# sch_main.net
KiCad netlist of a schematic drawn in Altium Designer
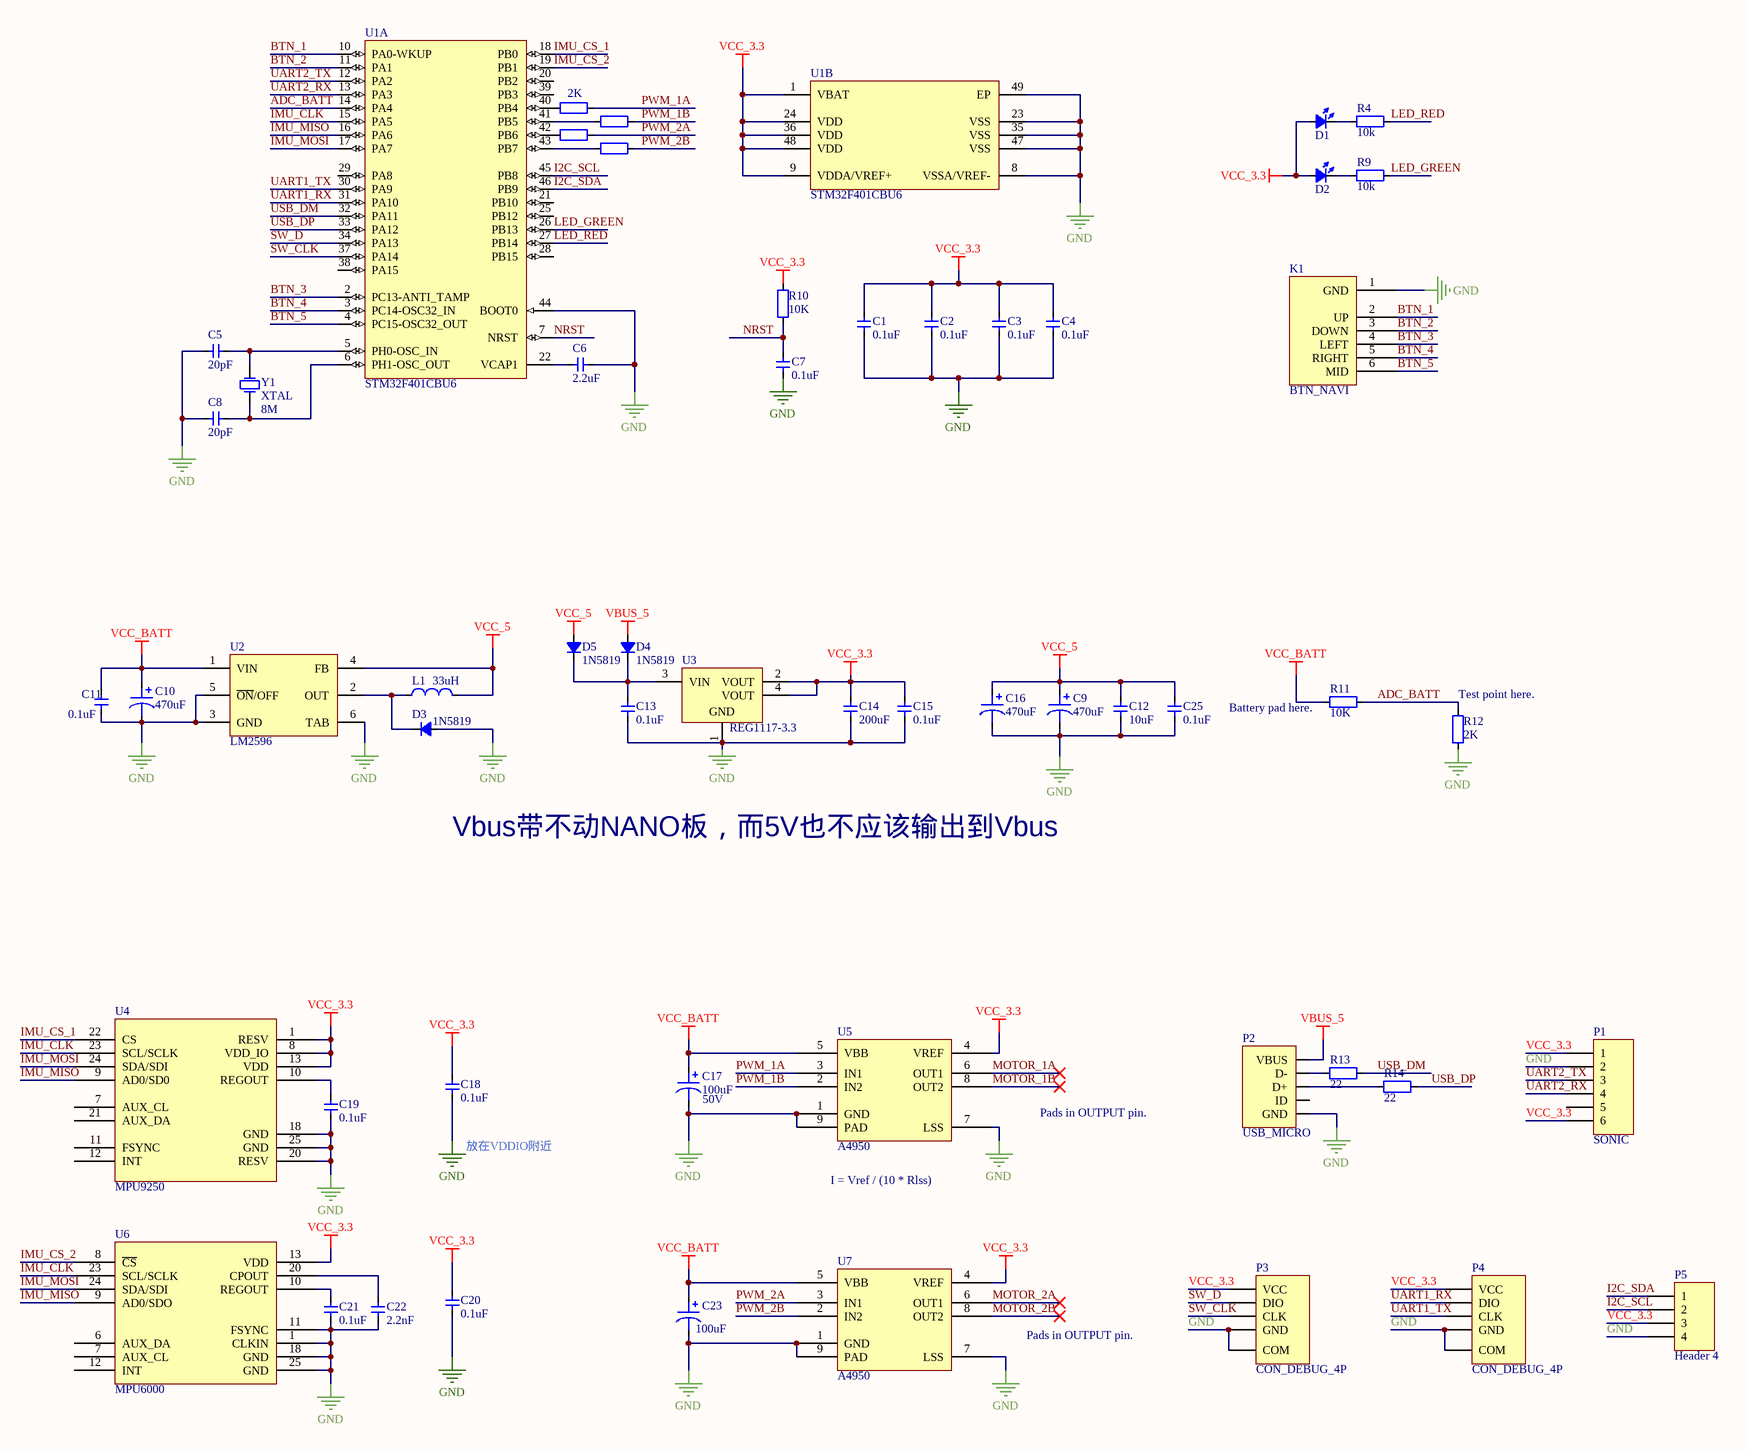
[diagram p0: sch_main.SchDoc]

(export (version "E")
  (design (tool "Eeschema 10.0.6"))
  (components
    (comp (ref "C1")
      (value "0.1uF")
      (footprint "CAP_0603")
      (description "Capacity")
      (fields (field (name "Comment") "CAP"))
      (libsource (lib "Charles") (part "CAP"))
    )
    (comp (ref "C2")
      (value "0.1uF")
      (footprint "CAP_0603")
      (description "Capacity")
      (fields (field (name "Comment") "CAP"))
      (libsource (lib "Charles") (part "CAP"))
    )
    (comp (ref "C3")
      (value "0.1uF")
      (footprint "CAP_0603")
      (description "Capacity")
      (fields (field (name "Comment") "CAP"))
      (libsource (lib "Charles") (part "CAP"))
    )
    (comp (ref "C4")
      (value "0.1uF")
      (footprint "CAP_0603")
      (description "Capacity")
      (fields (field (name "Comment") "CAP"))
      (libsource (lib "Charles") (part "CAP"))
    )
    (comp (ref "C5")
      (value "20pF")
      (footprint "CAP_0603")
      (description "Capacity")
      (fields (field (name "Comment") "CAP"))
      (libsource (lib "Charles") (part "CAP"))
    )
    (comp (ref "C6")
      (value "2.2uF")
      (footprint "CAP_0603")
      (description "Capacity")
      (fields (field (name "Comment") "CAP"))
      (libsource (lib "Charles") (part "CAP"))
    )
    (comp (ref "C7")
      (value "0.1uF")
      (footprint "CAP_0603")
      (description "Capacity")
      (fields (field (name "Comment") "CAP"))
      (libsource (lib "Charles") (part "CAP"))
    )
    (comp (ref "C8")
      (value "20pF")
      (footprint "CAP_0603")
      (description "Capacity")
      (fields (field (name "Comment") "CAP"))
      (libsource (lib "Charles") (part "CAP"))
    )
    (comp (ref "C9")
      (value "470uF")
      (footprint "CAP ALUM 6.6MM")
      (description "SMT Polarised Capacitor")
      (libsource (lib "Charles") (part "CAP_POL"))
    )
    (comp (ref "C10")
      (value "470uF")
      (footprint "CAP ALUM 6.6MM")
      (description "SMT Polarised Capacitor")
      (libsource (lib "Charles") (part "CAP_POL"))
    )
    (comp (ref "C11")
      (value "0.1uF")
      (footprint "CAP_0805")
      (description "Capacity")
      (fields (field (name "Comment") "CAP"))
      (libsource (lib "Charles") (part "CAP"))
    )
    (comp (ref "C12")
      (value "10uF")
      (footprint "CAP_TAN_B1210")
      (description "Capacity")
      (fields (field (name "Comment") "CAP"))
      (libsource (lib "Charles") (part "CAP"))
    )
    (comp (ref "C13")
      (value "0.1uF")
      (footprint "CAP_0805")
      (description "Capacity")
      (fields (field (name "Comment") "CAP"))
      (libsource (lib "Charles") (part "CAP"))
    )
    (comp (ref "C14")
      (value "200uF")
      (footprint "CAP_0805")
      (description "Capacity")
      (fields (field (name "Comment") "CAP"))
      (libsource (lib "Charles") (part "CAP"))
    )
    (comp (ref "C15")
      (value "0.1uF")
      (footprint "CAP_0603")
      (description "Capacity")
      (fields (field (name "Comment") "CAP"))
      (libsource (lib "Charles") (part "CAP"))
    )
    (comp (ref "C16")
      (value "470uF")
      (footprint "CAP ALUM 6.6MM")
      (description "SMT Polarised Capacitor")
      (libsource (lib "Charles") (part "CAP_POL"))
    )
    (comp (ref "C17")
      (value "100uF")
      (footprint "CAP ALUM 6.6MM")
      (description "SMT Polarised Capacitor")
      (fields (field (name "VOLTAGE") "50V"))
      (libsource (lib "Charles") (part "CAP_POL"))
    )
    (comp (ref "C18")
      (value "0.1uF")
      (footprint "CAP_0603")
      (description "Capacity")
      (fields (field (name "Comment") "CAP"))
      (libsource (lib "Charles") (part "CAP"))
    )
    (comp (ref "C19")
      (value "0.1uF")
      (footprint "CAP_0603")
      (description "Capacity")
      (fields (field (name "Comment") "CAP"))
      (libsource (lib "Charles") (part "CAP"))
    )
    (comp (ref "C20")
      (value "0.1uF")
      (footprint "CAP_0603")
      (description "Capacity")
      (fields (field (name "Comment") "CAP"))
      (libsource (lib "Charles") (part "CAP"))
    )
    (comp (ref "C21")
      (value "0.1uF")
      (footprint "CAP_0603")
      (description "Capacity")
      (fields (field (name "Comment") "CAP"))
      (libsource (lib "Charles") (part "CAP"))
    )
    (comp (ref "C22")
      (value "2.2nF")
      (footprint "CAP_0603")
      (description "Capacity")
      (fields (field (name "Comment") "CAP"))
      (libsource (lib "Charles") (part "CAP"))
    )
    (comp (ref "C23")
      (value "100uF")
      (footprint "CAP ALUM 6.6MM")
      (description "SMT Polarised Capacitor")
      (fields (field (name "VOLTAGE") "50V"))
      (libsource (lib "Charles") (part "CAP_POL"))
    )
    (comp (ref "C25")
      (value "0.1uF")
      (footprint "CAP_0603")
      (description "Capacity")
      (fields (field (name "Comment") "CAP"))
      (libsource (lib "Charles") (part "CAP"))
    )
    (comp (ref "D1") (value "LED") (footprint "LED_0603_GREEN") (libsource (lib "Charles") (part "LED")))
    (comp (ref "D2") (value "LED") (footprint "LED_0603_GREEN") (libsource (lib "Charles") (part "LED")))
    (comp (ref "D3")
      (value "1N5819")
      (footprint "DIO_SOD-123")
      (description "Diode")
      (libsource (lib "Charles") (part "Diode"))
    )
    (comp (ref "D4")
      (value "1N5819")
      (footprint "DIO_SOD-123")
      (description "Diode")
      (libsource (lib "Charles") (part "Diode"))
    )
    (comp (ref "D5")
      (value "1N5819")
      (footprint "DIO_SOD-123")
      (description "Diode")
      (libsource (lib "Charles") (part "Diode"))
    )
    (comp (ref "K1")
      (value "BTN_NAVI")
      (footprint "BTN_NAVI_10x10")
      (libsource (lib "Charles") (part "BTN_NAVI"))
    )
    (comp (ref "L1")
      (value "33uH")
      (footprint "IND_CDRH74")
      (description "Inductor")
      (fields (field (name "Comment") "IND"))
      (libsource (lib "Charles") (part "IND"))
    )
    (comp (ref "P1")
      (value "SONIC")
      (footprint "HDR1X6")
      (description "Header, 6-Pin")
      (fields (field (name "PUBLISHER") "Altium Limited"))
      (libsource (lib "Miscellaneous Connectors") (part "Header 6"))
    )
    (comp (ref "P2")
      (value "USB_MICRO")
      (footprint "USB_MICRO")
      (libsource (lib "Charles") (part "USB_MICRO"))
    )
    (comp (ref "P3")
      (value "CON_DEBUG_4P")
      (footprint "CON_DEBUG_4P_STD")
      (libsource (lib "Charles") (part "CON_DEBUG_4P"))
    )
    (comp (ref "P4")
      (value "CON_DEBUG_4P")
      (footprint "CON_DEBUG_4P_STD")
      (libsource (lib "Charles") (part "CON_DEBUG_4P"))
    )
    (comp (ref "P5")
      (value "Header 4")
      (footprint "HDR1X4")
      (description "Header, 4-Pin")
      (fields (field (name "PUBLISHER") "Altium Limited"))
      (libsource (lib "Miscellaneous Connectors") (part "Header 4"))
    )
    (comp (ref "R1")
      (value "2K")
      (footprint "RES_0603")
      (description "Resister")
      (fields (field (name "Comment") "RES"))
      (libsource (lib "Charles") (part "RES"))
    )
    (comp (ref "R3")
      (value "RES")
      (footprint "RES_0603")
      (description "Resister")
      (libsource (lib "Charles") (part "RES"))
    )
    (comp (ref "R4")
      (value "10k")
      (footprint "RES_0603")
      (description "Resister")
      (fields (field (name "Comment") "RES"))
      (libsource (lib "") (part "RES_2"))
    )
    (comp (ref "R6")
      (value "RES")
      (footprint "RES_0603")
      (description "Resister")
      (libsource (lib "Charles") (part "RES"))
    )
    (comp (ref "R8")
      (value "RES")
      (footprint "RES_0603")
      (description "Resister")
      (libsource (lib "Charles") (part "RES"))
    )
    (comp (ref "R9")
      (value "10k")
      (footprint "RES_0603")
      (description "Resister")
      (fields (field (name "Comment") "RES"))
      (libsource (lib "") (part "RES_2"))
    )
    (comp (ref "R10")
      (value "10K")
      (footprint "RES_0603")
      (description "Resister")
      (fields (field (name "Comment") "RES"))
      (libsource (lib "") (part "RES_1"))
    )
    (comp (ref "R11")
      (value "10K")
      (footprint "RES_0603")
      (description "Resister")
      (fields (field (name "Comment") "RES"))
      (libsource (lib "Charles") (part "RES"))
    )
    (comp (ref "R12")
      (value "2K")
      (footprint "RES_0603")
      (description "Resister")
      (fields (field (name "Comment") "RES"))
      (libsource (lib "") (part "RES_3"))
    )
    (comp (ref "R13")
      (value "22")
      (footprint "RES_0603")
      (description "Resister")
      (fields (field (name "Comment") "RES"))
      (libsource (lib "Charles") (part "RES"))
    )
    (comp (ref "R14")
      (value "22")
      (footprint "RES_0603")
      (description "Resister")
      (fields (field (name "Comment") "RES"))
      (libsource (lib "Charles") (part "RES"))
    )
    (comp (ref "U1")
      (value "STM32F401CBU6")
      (footprint "STM-UFQFPN48_N")
      (fields (field (name "MANUFACTURER") "STMicroelectronics"))
      (libsource (lib "STMicroelectronics STM32 F4") (part "STM32F401CBU6"))
    )
    (comp (ref "U2")
      (value "LM2596")
      (footprint "LM2596")
      (description "Power")
      (libsource (lib "Charles") (part "LM2596"))
    )
    (comp (ref "U3")
      (value "REG1117-3.3")
      (footprint "TI-DCY4_N")
      (fields (field (name "MANUFACTURER") "Texas Instruments"))
      (libsource (lib "TI Power Management Linear Regulator Single Channel LDO (400-7500mA)") (part "REG1117-3.3"))
    )
    (comp (ref "U4")
      (value "MPU9250")
      (footprint "MPU9250")
      (description "Sensor")
      (libsource (lib "Charles") (part "MPU9250"))
    )
    (comp (ref "U5")
      (value "A4950")
      (footprint "A4950")
      (description "Dual N-MOS, 40V, 3.5A.")
      (libsource (lib "Charles") (part "A4950"))
    )
    (comp (ref "U6")
      (value "MPU6000")
      (footprint "MPU6000")
      (description "IMU 6axis, (左下方引脚全部悬空)")
      (libsource (lib "Charles") (part "MPU6000"))
    )
    (comp (ref "U7")
      (value "A4950")
      (footprint "A4950")
      (description "Dual N-MOS, 40V, 3.5A.")
      (libsource (lib "Charles") (part "A4950"))
    )
    (comp (ref "Y1")
      (value "XTAL")
      (footprint "XTAL_8M")
      (fields (field (name "FREQUENCY") "8M"))
      (libsource (lib "Charles") (part "XTAL"))
    )
  )
  (nets
    (net (code "1") (name "/ADC_BATT") (class "Default")
      (node (ref "R11") (pin "2") (pinfunction "2_2") (pintype "passive"))
      (node (ref "R12") (pin "1") (pinfunction "1_1") (pintype "passive"))
      (node (ref "U1") (pin "14") (pinfunction "PA4_14") (pintype "bidirectional"))
    )
    (net (code "2") (name "/BTN_1") (class "Default")
      (node (ref "K1") (pin "2") (pinfunction "UP_2") (pintype "passive"))
      (node (ref "U1") (pin "10") (pinfunction "PA0-WKUP_10") (pintype "bidirectional"))
    )
    (net (code "3") (name "/BTN_2") (class "Default")
      (node (ref "K1") (pin "3") (pinfunction "DOWN_3") (pintype "passive"))
      (node (ref "U1") (pin "11") (pinfunction "PA1_11") (pintype "bidirectional"))
    )
    (net (code "4") (name "/BTN_3") (class "Default")
      (node (ref "K1") (pin "4") (pinfunction "LEFT_4") (pintype "passive"))
      (node (ref "U1") (pin "2") (pinfunction "PC13-ANTI_TAMP_2") (pintype "bidirectional"))
    )
    (net (code "5") (name "/BTN_4") (class "Default")
      (node (ref "K1") (pin "5") (pinfunction "RIGHT_5") (pintype "passive"))
      (node (ref "U1") (pin "3") (pinfunction "PC14-OSC32_IN_3") (pintype "bidirectional"))
    )
    (net (code "6") (name "/BTN_5") (class "Default")
      (node (ref "K1") (pin "6") (pinfunction "MID_6") (pintype "passive"))
      (node (ref "U1") (pin "4") (pinfunction "PC15-OSC32_OUT_4") (pintype "bidirectional"))
    )
    (net (code "7") (name "/I2C_SCL") (class "Default")
      (node (ref "P5") (pin "2") (pinfunction "2_2") (pintype "passive"))
      (node (ref "U1") (pin "45") (pinfunction "PB8_45") (pintype "bidirectional"))
    )
    (net (code "8") (name "/I2C_SDA") (class "Default")
      (node (ref "P5") (pin "1") (pinfunction "1_1") (pintype "passive"))
      (node (ref "U1") (pin "46") (pinfunction "PB9_46") (pintype "bidirectional"))
    )
    (net (code "9") (name "/IMU_CLK") (class "Default")
      (node (ref "U1") (pin "15") (pinfunction "PA5_15") (pintype "bidirectional"))
      (node (ref "U4") (pin "23") (pinfunction "SCL/SCLK_23") (pintype "passive"))
      (node (ref "U6") (pin "23") (pinfunction "SCL/SCLK_23") (pintype "passive"))
    )
    (net (code "10") (name "/IMU_CS_1") (class "Default")
      (node (ref "U1") (pin "18") (pinfunction "PB0_18") (pintype "bidirectional"))
      (node (ref "U4") (pin "22") (pinfunction "CS_22") (pintype "passive"))
    )
    (net (code "11") (name "/IMU_CS_2") (class "Default")
      (node (ref "U1") (pin "19") (pinfunction "PB1_19") (pintype "bidirectional"))
      (node (ref "U6") (pin "8") (pinfunction "~{CS}_8") (pintype "passive"))
    )
    (net (code "12") (name "/IMU_MISO") (class "Default")
      (node (ref "U1") (pin "16") (pinfunction "PA6_16") (pintype "bidirectional"))
      (node (ref "U4") (pin "9") (pinfunction "AD0/SD0_9") (pintype "passive"))
      (node (ref "U6") (pin "9") (pinfunction "AD0/SDO_9") (pintype "passive"))
    )
    (net (code "13") (name "/IMU_MOSI") (class "Default")
      (node (ref "U1") (pin "17") (pinfunction "PA7_17") (pintype "bidirectional"))
      (node (ref "U4") (pin "24") (pinfunction "SDA/SDI_24") (pintype "passive"))
      (node (ref "U6") (pin "24") (pinfunction "SDA/SDI_24") (pintype "passive"))
    )
    (net (code "14") (name "/LED_GREEN") (class "Default")
      (node (ref "R9") (pin "1") (pinfunction "1_1") (pintype "passive"))
      (node (ref "U1") (pin "26") (pinfunction "PB13_26") (pintype "bidirectional"))
    )
    (net (code "15") (name "/LED_RED") (class "Default")
      (node (ref "R4") (pin "1") (pinfunction "1_1") (pintype "passive"))
      (node (ref "U1") (pin "27") (pinfunction "PB14_27") (pintype "bidirectional"))
    )
    (net (code "16") (name "/MOTOR_1A") (class "Default")
      (node (ref "U5") (pin "6") (pinfunction "OUT1_6") (pintype "passive+no_connect"))
    )
    (net (code "17") (name "/MOTOR_1B") (class "Default")
      (node (ref "U5") (pin "8") (pinfunction "OUT2_8") (pintype "passive+no_connect"))
    )
    (net (code "18") (name "/MOTOR_2A") (class "Default")
      (node (ref "U7") (pin "6") (pinfunction "OUT1_6") (pintype "passive+no_connect"))
    )
    (net (code "19") (name "/MOTOR_2B") (class "Default")
      (node (ref "U7") (pin "8") (pinfunction "OUT2_8") (pintype "passive+no_connect"))
    )
    (net (code "20") (name "/NRST") (class "Default")
      (node (ref "C7") (pin "2") (pinfunction "2_2") (pintype "passive"))
      (node (ref "R10") (pin "1") (pinfunction "1_1") (pintype "passive"))
      (node (ref "U1") (pin "7") (pinfunction "NRST_7") (pintype "bidirectional"))
    )
    (net (code "21") (name "/PWM_1A") (class "Default")
      (node (ref "R1") (pin "2") (pinfunction "2_2") (pintype "passive"))
      (node (ref "U5") (pin "3") (pinfunction "IN1_3") (pintype "passive"))
    )
    (net (code "22") (name "/PWM_1B") (class "Default")
      (node (ref "R3") (pin "2") (pinfunction "2_2") (pintype "passive"))
      (node (ref "U5") (pin "2") (pinfunction "IN2_2") (pintype "passive"))
    )
    (net (code "23") (name "/PWM_2A") (class "Default")
      (node (ref "R6") (pin "2") (pinfunction "2_2") (pintype "passive"))
      (node (ref "U7") (pin "3") (pinfunction "IN1_3") (pintype "passive"))
    )
    (net (code "24") (name "/PWM_2B") (class "Default")
      (node (ref "R8") (pin "2") (pinfunction "2_2") (pintype "passive"))
      (node (ref "U7") (pin "2") (pinfunction "IN2_2") (pintype "passive"))
    )
    (net (code "25") (name "/SW_CLK") (class "Default")
      (node (ref "P3") (pin "3") (pinfunction "CLK_3") (pintype "passive"))
      (node (ref "U1") (pin "37") (pinfunction "PA14_37") (pintype "bidirectional"))
    )
    (net (code "26") (name "/SW_D") (class "Default")
      (node (ref "P3") (pin "2") (pinfunction "DIO_2") (pintype "passive"))
      (node (ref "U1") (pin "34") (pinfunction "PA13_34") (pintype "bidirectional"))
    )
    (net (code "27") (name "/UART1_RX") (class "Default")
      (node (ref "P4") (pin "2") (pinfunction "DIO_2") (pintype "passive"))
      (node (ref "U1") (pin "31") (pinfunction "PA10_31") (pintype "bidirectional"))
    )
    (net (code "28") (name "/UART1_TX") (class "Default")
      (node (ref "P4") (pin "3") (pinfunction "CLK_3") (pintype "passive"))
      (node (ref "U1") (pin "30") (pinfunction "PA9_30") (pintype "bidirectional"))
    )
    (net (code "29") (name "/UART2_RX") (class "Default")
      (node (ref "P1") (pin "4") (pinfunction "4_4") (pintype "passive"))
      (node (ref "U1") (pin "13") (pinfunction "PA3_13") (pintype "bidirectional"))
    )
    (net (code "30") (name "/UART2_TX") (class "Default")
      (node (ref "P1") (pin "3") (pinfunction "3_3") (pintype "passive"))
      (node (ref "U1") (pin "12") (pinfunction "PA2_12") (pintype "bidirectional"))
    )
    (net (code "31") (name "/USB_DM") (class "Default")
      (node (ref "R13") (pin "2") (pinfunction "2_2") (pintype "passive"))
      (node (ref "U1") (pin "32") (pinfunction "PA11_32") (pintype "bidirectional"))
    )
    (net (code "32") (name "/USB_DP") (class "Default")
      (node (ref "R14") (pin "2") (pinfunction "2_2") (pintype "passive"))
      (node (ref "U1") (pin "33") (pinfunction "PA12_33") (pintype "bidirectional"))
    )
    (net (code "33") (name "GND") (class "Default")
      (node (ref "C1") (pin "1") (pinfunction "1_1") (pintype "passive"))
      (node (ref "C10") (pin "2") (pinfunction "2_2") (pintype "passive"))
      (node (ref "C11") (pin "1") (pinfunction "1_1") (pintype "passive"))
      (node (ref "C12") (pin "1") (pinfunction "1_1") (pintype "passive"))
      (node (ref "C13") (pin "1") (pinfunction "1_1") (pintype "passive"))
      (node (ref "C14") (pin "1") (pinfunction "1_1") (pintype "passive"))
      (node (ref "C15") (pin "1") (pinfunction "1_1") (pintype "passive"))
      (node (ref "C16") (pin "2") (pinfunction "2_2") (pintype "passive"))
      (node (ref "C17") (pin "2") (pinfunction "2_2") (pintype "passive"))
      (node (ref "C18") (pin "1") (pinfunction "1_1") (pintype "passive"))
      (node (ref "C19") (pin "1") (pinfunction "1_1") (pintype "passive"))
      (node (ref "C2") (pin "1") (pinfunction "1_1") (pintype "passive"))
      (node (ref "C20") (pin "1") (pinfunction "1_1") (pintype "passive"))
      (node (ref "C21") (pin "1") (pinfunction "1_1") (pintype "passive"))
      (node (ref "C22") (pin "1") (pinfunction "1_1") (pintype "passive"))
      (node (ref "C23") (pin "2") (pinfunction "2_2") (pintype "passive"))
      (node (ref "C25") (pin "1") (pinfunction "1_1") (pintype "passive"))
      (node (ref "C3") (pin "1") (pinfunction "1_1") (pintype "passive"))
      (node (ref "C4") (pin "1") (pinfunction "1_1") (pintype "passive"))
      (node (ref "C5") (pin "1") (pinfunction "1_1") (pintype "passive"))
      (node (ref "C6") (pin "2") (pinfunction "2_2") (pintype "passive"))
      (node (ref "C7") (pin "1") (pinfunction "1_1") (pintype "passive"))
      (node (ref "C8") (pin "1") (pinfunction "1_1") (pintype "passive"))
      (node (ref "C9") (pin "2") (pinfunction "2_2") (pintype "passive"))
      (node (ref "D3") (pin "1") (pinfunction "A_1") (pintype "passive"))
      (node (ref "K1") (pin "1") (pinfunction "GND_1") (pintype "passive"))
      (node (ref "P1") (pin "2") (pinfunction "2_2") (pintype "passive"))
      (node (ref "P2") (pin "5") (pinfunction "GND_5") (pintype "passive"))
      (node (ref "P3") (pin "4") (pinfunction "GND_4") (pintype "passive"))
      (node (ref "P3") (pin "5") (pinfunction "COM_5") (pintype "passive"))
      (node (ref "P4") (pin "4") (pinfunction "GND_4") (pintype "passive"))
      (node (ref "P4") (pin "5") (pinfunction "COM_5") (pintype "passive"))
      (node (ref "P5") (pin "4") (pinfunction "4_4") (pintype "passive"))
      (node (ref "R12") (pin "2") (pinfunction "2_2") (pintype "passive"))
      (node (ref "U1") (pin "23") (pinfunction "VSS_23") (pintype "power_in"))
      (node (ref "U1") (pin "35") (pinfunction "VSS_35") (pintype "power_in"))
      (node (ref "U1") (pin "44") (pinfunction "BOOT0_44") (pintype "input"))
      (node (ref "U1") (pin "47") (pinfunction "VSS_47") (pintype "power_in"))
      (node (ref "U1") (pin "49") (pinfunction "EP_49") (pintype "power_in"))
      (node (ref "U1") (pin "8") (pinfunction "VSSA/VREF-_8") (pintype "power_in"))
      (node (ref "U2") (pin "3") (pinfunction "GND_3") (pintype "power_in"))
      (node (ref "U2") (pin "5") (pinfunction "~{ON}/OFF_5") (pintype "passive"))
      (node (ref "U2") (pin "6") (pinfunction "TAB_6") (pintype "power_in"))
      (node (ref "U3") (pin "1") (pinfunction "GND_1") (pintype "power_in"))
      (node (ref "U4") (pin "18") (pinfunction "GND_18") (pintype "passive"))
      (node (ref "U4") (pin "20") (pinfunction "RESV_20") (pintype "passive"))
      (node (ref "U4") (pin "25") (pinfunction "GND_25") (pintype "passive"))
      (node (ref "U5") (pin "1") (pinfunction "GND_1") (pintype "passive"))
      (node (ref "U5") (pin "7") (pinfunction "LSS_7") (pintype "passive"))
      (node (ref "U5") (pin "9") (pinfunction "PAD_9") (pintype "passive"))
      (node (ref "U6") (pin "1") (pinfunction "CLKIN_1") (pintype "passive"))
      (node (ref "U6") (pin "11") (pinfunction "FSYNC_11") (pintype "passive"))
      (node (ref "U6") (pin "18") (pinfunction "GND_18") (pintype "passive"))
      (node (ref "U6") (pin "25") (pinfunction "GND_25") (pintype "passive"))
      (node (ref "U7") (pin "1") (pinfunction "GND_1") (pintype "passive"))
      (node (ref "U7") (pin "7") (pinfunction "LSS_7") (pintype "passive"))
      (node (ref "U7") (pin "9") (pinfunction "PAD_9") (pintype "passive"))
    )
    (net (code "34") (name "Net-(D1-K)") (class "Default")
      (node (ref "D1") (pin "2") (pinfunction "K_2") (pintype "passive"))
      (node (ref "R4") (pin "2") (pinfunction "2_2") (pintype "passive"))
    )
    (net (code "35") (name "Net-(D2-K)") (class "Default")
      (node (ref "D2") (pin "2") (pinfunction "K_2") (pintype "passive"))
      (node (ref "R9") (pin "2") (pinfunction "2_2") (pintype "passive"))
    )
    (net (code "36") (name "Net-(D3-K)") (class "Default")
      (node (ref "D3") (pin "2") (pinfunction "K_2") (pintype "passive"))
      (node (ref "L1") (pin "1") (pinfunction "1_1") (pintype "passive"))
      (node (ref "U2") (pin "2") (pinfunction "OUT_2") (pintype "power_in"))
    )
    (net (code "37") (name "Net-(D4-K)") (class "Default")
      (node (ref "C13") (pin "2") (pinfunction "2_2") (pintype "passive"))
      (node (ref "D4") (pin "2") (pinfunction "K_2") (pintype "passive"))
      (node (ref "D5") (pin "2") (pinfunction "K_2") (pintype "passive"))
      (node (ref "U3") (pin "3") (pinfunction "VIN_3") (pintype "power_in"))
    )
    (net (code "38") (name "Net-(P2-D+)") (class "Default")
      (node (ref "P2") (pin "3") (pinfunction "D+_3") (pintype "passive"))
      (node (ref "R14") (pin "1") (pinfunction "1_1") (pintype "passive"))
    )
    (net (code "39") (name "Net-(P2-D-)") (class "Default")
      (node (ref "P2") (pin "2") (pinfunction "D-_2") (pintype "passive"))
      (node (ref "R13") (pin "1") (pinfunction "1_1") (pintype "passive"))
    )
    (net (code "40") (name "Net-(U1A-PB4)") (class "Default")
      (node (ref "R1") (pin "1") (pinfunction "1_1") (pintype "passive"))
      (node (ref "U1") (pin "40") (pinfunction "PB4_40") (pintype "bidirectional"))
    )
    (net (code "41") (name "Net-(U1A-PB5)") (class "Default")
      (node (ref "R3") (pin "1") (pinfunction "1_1") (pintype "passive"))
      (node (ref "U1") (pin "41") (pinfunction "PB5_41") (pintype "bidirectional"))
    )
    (net (code "42") (name "Net-(U1A-PB6)") (class "Default")
      (node (ref "R6") (pin "1") (pinfunction "1_1") (pintype "passive"))
      (node (ref "U1") (pin "42") (pinfunction "PB6_42") (pintype "bidirectional"))
    )
    (net (code "43") (name "Net-(U1A-PB7)") (class "Default")
      (node (ref "R8") (pin "1") (pinfunction "1_1") (pintype "passive"))
      (node (ref "U1") (pin "43") (pinfunction "PB7_43") (pintype "bidirectional"))
    )
    (net (code "44") (name "Net-(U1A-PH0-OSC_IN)") (class "Default")
      (node (ref "C5") (pin "2") (pinfunction "2_2") (pintype "passive"))
      (node (ref "U1") (pin "5") (pinfunction "PH0-OSC_IN_5") (pintype "bidirectional"))
      (node (ref "Y1") (pin "2") (pinfunction "OSC2_2") (pintype "passive"))
    )
    (net (code "45") (name "Net-(U1A-PH1-OSC_OUT)") (class "Default")
      (node (ref "C8") (pin "2") (pinfunction "2_2") (pintype "passive"))
      (node (ref "U1") (pin "6") (pinfunction "PH1-OSC_OUT_6") (pintype "bidirectional"))
      (node (ref "Y1") (pin "1") (pinfunction "OSC1_1") (pintype "passive"))
    )
    (net (code "46") (name "Net-(U1A-VCAP1)") (class "Default")
      (node (ref "C6") (pin "1") (pinfunction "1_1") (pintype "passive"))
      (node (ref "U1") (pin "22") (pinfunction "VCAP1_22") (pintype "power_in"))
    )
    (net (code "47") (name "Net-(U4-REGOUT)") (class "Default")
      (node (ref "C19") (pin "2") (pinfunction "2_2") (pintype "passive"))
      (node (ref "U4") (pin "10") (pinfunction "REGOUT_10") (pintype "passive"))
    )
    (net (code "48") (name "Net-(U6-CPOUT)") (class "Default")
      (node (ref "C22") (pin "2") (pinfunction "2_2") (pintype "passive"))
      (node (ref "U6") (pin "20") (pinfunction "CPOUT_20") (pintype "passive"))
    )
    (net (code "49") (name "Net-(U6-REGOUT)") (class "Default")
      (node (ref "C21") (pin "2") (pinfunction "2_2") (pintype "passive"))
      (node (ref "U6") (pin "10") (pinfunction "REGOUT_10") (pintype "passive"))
    )
    (net (code "50") (name "VBUS_5") (class "Default")
      (node (ref "D4") (pin "1") (pinfunction "A_1") (pintype "passive"))
      (node (ref "P2") (pin "1") (pinfunction "VBUS_1") (pintype "passive"))
    )
    (net (code "51") (name "VCC_3.3") (class "Default")
      (node (ref "C1") (pin "2") (pinfunction "2_2") (pintype "passive"))
      (node (ref "C14") (pin "2") (pinfunction "2_2") (pintype "passive"))
      (node (ref "C15") (pin "2") (pinfunction "2_2") (pintype "passive"))
      (node (ref "C18") (pin "2") (pinfunction "2_2") (pintype "passive"))
      (node (ref "C2") (pin "2") (pinfunction "2_2") (pintype "passive"))
      (node (ref "C20") (pin "2") (pinfunction "2_2") (pintype "passive"))
      (node (ref "C3") (pin "2") (pinfunction "2_2") (pintype "passive"))
      (node (ref "C4") (pin "2") (pinfunction "2_2") (pintype "passive"))
      (node (ref "D1") (pin "1") (pinfunction "A_1") (pintype "passive"))
      (node (ref "D2") (pin "1") (pinfunction "A_1") (pintype "passive"))
      (node (ref "P1") (pin "1") (pinfunction "1_1") (pintype "passive"))
      (node (ref "P1") (pin "6") (pinfunction "6_6") (pintype "passive"))
      (node (ref "P3") (pin "1") (pinfunction "VCC_1") (pintype "passive"))
      (node (ref "P4") (pin "1") (pinfunction "VCC_1") (pintype "passive"))
      (node (ref "P5") (pin "3") (pinfunction "3_3") (pintype "passive"))
      (node (ref "R10") (pin "2") (pinfunction "2_2") (pintype "passive"))
      (node (ref "U1") (pin "1") (pinfunction "VBAT_1") (pintype "power_in"))
      (node (ref "U1") (pin "24") (pinfunction "VDD_24") (pintype "power_in"))
      (node (ref "U1") (pin "36") (pinfunction "VDD_36") (pintype "power_in"))
      (node (ref "U1") (pin "48") (pinfunction "VDD_48") (pintype "power_in"))
      (node (ref "U1") (pin "9") (pinfunction "VDDA/VREF+_9") (pintype "power_in"))
      (node (ref "U3") (pin "2") (pinfunction "VOUT_2") (pintype "power_in"))
      (node (ref "U3") (pin "4") (pinfunction "VOUT_4") (pintype "power_in"))
      (node (ref "U4") (pin "1") (pinfunction "RESV_1") (pintype "passive"))
      (node (ref "U4") (pin "13") (pinfunction "VDD_13") (pintype "passive"))
      (node (ref "U4") (pin "8") (pinfunction "VDD_IO_8") (pintype "passive"))
      (node (ref "U5") (pin "4") (pinfunction "VREF_4") (pintype "passive"))
      (node (ref "U6") (pin "13") (pinfunction "VDD_13") (pintype "passive"))
      (node (ref "U7") (pin "4") (pinfunction "VREF_4") (pintype "passive"))
    )
    (net (code "52") (name "VCC_5") (class "Default")
      (node (ref "C12") (pin "2") (pinfunction "2_2") (pintype "passive"))
      (node (ref "C16") (pin "1") (pinfunction "1_1") (pintype "passive"))
      (node (ref "C25") (pin "2") (pinfunction "2_2") (pintype "passive"))
      (node (ref "C9") (pin "1") (pinfunction "1_1") (pintype "passive"))
      (node (ref "D5") (pin "1") (pinfunction "A_1") (pintype "passive"))
      (node (ref "L1") (pin "2") (pinfunction "2_2") (pintype "passive"))
      (node (ref "U2") (pin "4") (pinfunction "FB_4") (pintype "passive"))
    )
    (net (code "53") (name "VCC_BATT") (class "Default")
      (node (ref "C10") (pin "1") (pinfunction "1_1") (pintype "passive"))
      (node (ref "C11") (pin "2") (pinfunction "2_2") (pintype "passive"))
      (node (ref "C17") (pin "1") (pinfunction "1_1") (pintype "passive"))
      (node (ref "C23") (pin "1") (pinfunction "1_1") (pintype "passive"))
      (node (ref "R11") (pin "1") (pinfunction "1_1") (pintype "passive"))
      (node (ref "U2") (pin "1") (pinfunction "VIN_1") (pintype "power_in"))
      (node (ref "U5") (pin "5") (pinfunction "VBB_5") (pintype "passive"))
      (node (ref "U7") (pin "5") (pinfunction "VBB_5") (pintype "passive"))
    )
    (net (code "54") (name "unconnected-(P1-Pad5)") (class "Default")
      (node (ref "P1") (pin "5") (pinfunction "5_5") (pintype "passive"))
    )
    (net (code "55") (name "unconnected-(P2-ID-Pad4)") (class "Default")
      (node (ref "P2") (pin "4") (pinfunction "ID_4") (pintype "passive"))
    )
    (net (code "56") (name "unconnected-(U1A-PA8-Pad29)") (class "Default")
      (node (ref "U1") (pin "29") (pinfunction "PA8_29") (pintype "bidirectional"))
    )
    (net (code "57") (name "unconnected-(U1A-PA15-Pad38)") (class "Default")
      (node (ref "U1") (pin "38") (pinfunction "PA15_38") (pintype "bidirectional"))
    )
    (net (code "58") (name "unconnected-(U1A-PB2-Pad20)") (class "Default")
      (node (ref "U1") (pin "20") (pinfunction "PB2_20") (pintype "bidirectional"))
    )
    (net (code "59") (name "unconnected-(U1A-PB3-Pad39)") (class "Default")
      (node (ref "U1") (pin "39") (pinfunction "PB3_39") (pintype "bidirectional"))
    )
    (net (code "60") (name "unconnected-(U1A-PB10-Pad21)") (class "Default")
      (node (ref "U1") (pin "21") (pinfunction "PB10_21") (pintype "bidirectional"))
    )
    (net (code "61") (name "unconnected-(U1A-PB12-Pad25)") (class "Default")
      (node (ref "U1") (pin "25") (pinfunction "PB12_25") (pintype "bidirectional"))
    )
    (net (code "62") (name "unconnected-(U1A-PB15-Pad28)") (class "Default")
      (node (ref "U1") (pin "28") (pinfunction "PB15_28") (pintype "bidirectional"))
    )
    (net (code "63") (name "unconnected-(U4-AUX_CL-Pad7)") (class "Default")
      (node (ref "U4") (pin "7") (pinfunction "AUX_CL_7") (pintype "passive"))
    )
    (net (code "64") (name "unconnected-(U4-AUX_DA-Pad21)") (class "Default")
      (node (ref "U4") (pin "21") (pinfunction "AUX_DA_21") (pintype "passive"))
    )
    (net (code "65") (name "unconnected-(U4-FSYNC-Pad11)") (class "Default")
      (node (ref "U4") (pin "11") (pinfunction "FSYNC_11") (pintype "passive"))
    )
    (net (code "66") (name "unconnected-(U4-INT-Pad12)") (class "Default")
      (node (ref "U4") (pin "12") (pinfunction "INT_12") (pintype "passive"))
    )
    (net (code "67") (name "unconnected-(U6-AUX_CL-Pad7)") (class "Default")
      (node (ref "U6") (pin "7") (pinfunction "AUX_CL_7") (pintype "passive"))
    )
    (net (code "68") (name "unconnected-(U6-AUX_DA-Pad6)") (class "Default")
      (node (ref "U6") (pin "6") (pinfunction "AUX_DA_6") (pintype "passive"))
    )
    (net (code "69") (name "unconnected-(U6-INT-Pad12)") (class "Default")
      (node (ref "U6") (pin "12") (pinfunction "INT_12") (pintype "passive"))
    )
  )
)
